# DeadHorsePCB.net
KiCad netlist of a schematic drawn in EAGLE
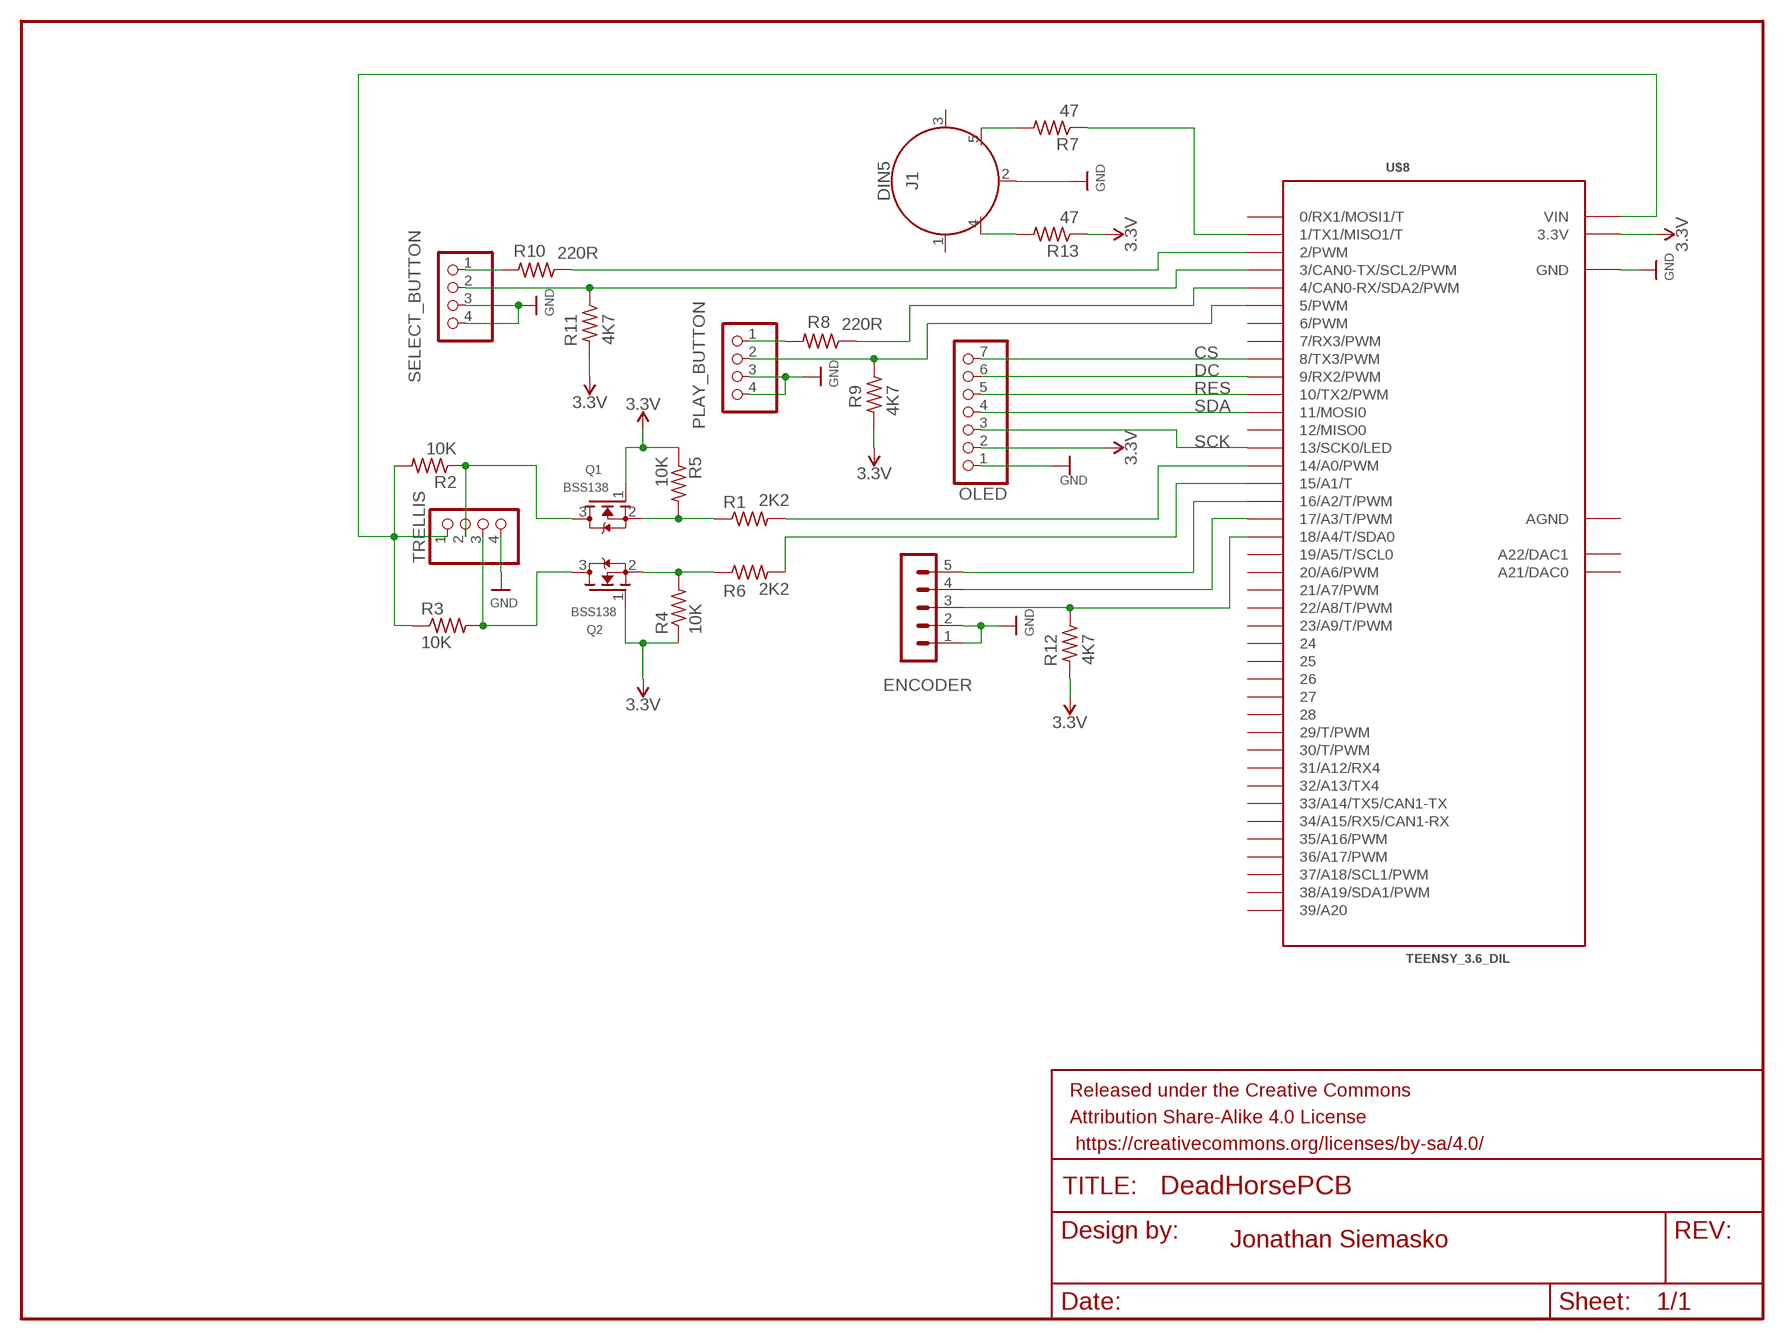
[diagram p0: schematic, sheet 1]

(export (version "E")
  (design (tool "Eeschema 10.0.6"))
  (components
    (comp (ref "ENCODER")
      (value "MA05-1")
      (footprint "eagle-import:MA05-1")
      (libsource (lib "eagle-import") (part "MA05-1"))
    )
    (comp (ref "FRAME1")
      (value "FRAME-LETTER")
      (footprint "eagle-import:CREATIVE_COMMONS")
      (libsource (lib "eagle-import") (part "FRAME-LETTER"))
    )
    (comp (ref "J1")
      (value "DIN5")
      (footprint "eagle-import:DIN5-RA-PTH")
      (libsource (lib "eagle-import") (part "DIN5"))
    )
    (comp (ref "OLED")
      (value "OLED")
      (footprint "eagle-import:1X07")
      (libsource (lib "eagle-import") (part "PINHD-1X7"))
    )
    (comp (ref "PLAY_BUTTON")
      (value "PlayBtn")
      (footprint "eagle-import:1X04")
      (libsource (lib "eagle-import") (part "PINHD-1X4"))
    )
    (comp (ref "Q1")
      (value "BSS138")
      (footprint "eagle-import:SOT23")
      (libsource (lib "eagle-import") (part "MOSFET-NREFLOW"))
    )
    (comp (ref "Q2")
      (value "BSS138")
      (footprint "eagle-import:SOT23")
      (libsource (lib "eagle-import") (part "MOSFET-NREFLOW"))
    )
    (comp (ref "R1")
      (value "2K2")
      (footprint "eagle-import:R0805")
      (libsource (lib "eagle-import") (part "R-US_R0805"))
    )
    (comp (ref "R2")
      (value "10K")
      (footprint "eagle-import:R0805")
      (libsource (lib "eagle-import") (part "R-US_R0805"))
    )
    (comp (ref "R3")
      (value "10K")
      (footprint "eagle-import:R0805")
      (libsource (lib "eagle-import") (part "R-US_R0805"))
    )
    (comp (ref "R4")
      (value "10K")
      (footprint "eagle-import:R0805")
      (libsource (lib "eagle-import") (part "R-US_R0805"))
    )
    (comp (ref "R5")
      (value "10K")
      (footprint "eagle-import:R0805")
      (libsource (lib "eagle-import") (part "R-US_R0805"))
    )
    (comp (ref "R6")
      (value "2K2")
      (footprint "eagle-import:R0805")
      (libsource (lib "eagle-import") (part "R-US_R0805"))
    )
    (comp (ref "R7")
      (value "47")
      (footprint "eagle-import:R0805")
      (libsource (lib "eagle-import") (part "R-US_R0805"))
    )
    (comp (ref "R8")
      (value "220R")
      (footprint "eagle-import:R0805")
      (libsource (lib "eagle-import") (part "R-US_R0805"))
    )
    (comp (ref "R9")
      (value "4K7")
      (footprint "eagle-import:R0805")
      (libsource (lib "eagle-import") (part "R-US_R0805"))
    )
    (comp (ref "R10")
      (value "220R")
      (footprint "eagle-import:R0805")
      (libsource (lib "eagle-import") (part "R-US_R0805"))
    )
    (comp (ref "R11")
      (value "4K7")
      (footprint "eagle-import:R0805")
      (libsource (lib "eagle-import") (part "R-US_R0805"))
    )
    (comp (ref "R12")
      (value "4K7")
      (footprint "eagle-import:R0805")
      (libsource (lib "eagle-import") (part "R-US_R0805"))
    )
    (comp (ref "R13")
      (value "47")
      (footprint "eagle-import:R0805")
      (libsource (lib "eagle-import") (part "R-US_R0805"))
    )
    (comp (ref "SELECT_BUTTON")
      (value "SelectBtn")
      (footprint "eagle-import:1X04")
      (libsource (lib "eagle-import") (part "PINHD-1X4"))
    )
    (comp (ref "TRELLIS")
      (value "TRELLIS")
      (footprint "eagle-import:1X04")
      (libsource (lib "eagle-import") (part "PINHD-1X4"))
    )
    (comp (ref "U$8")
      (value "TEENSY_3.6_DIL")
      (footprint "eagle-import:TEENSY_3.6_DIL")
      (libsource (lib "eagle-import") (part "TEENSY_3.6_DIL"))
    )
  )
  (nets
    (net (code "1") (name "/AGND") (class "Default")
      (node (ref "U$8") (pin "AGND") (pinfunction "AGND_AGND") (pintype "power_in"))
    )
    (net (code "2") (name "/CS") (class "Default")
      (node (ref "OLED") (pin "7") (pinfunction "7_7") (pintype "passive"))
      (node (ref "U$8") (pin "8") (pinfunction "8/TX3/PWM_8") (pintype "bidirectional"))
    )
    (net (code "3") (name "/DC") (class "Default")
      (node (ref "OLED") (pin "6") (pinfunction "6_6") (pintype "passive"))
      (node (ref "U$8") (pin "9") (pinfunction "9/RX2/PWM_9") (pintype "bidirectional"))
    )
    (net (code "4") (name "/RES") (class "Default")
      (node (ref "OLED") (pin "5") (pinfunction "5_5") (pintype "passive"))
      (node (ref "U$8") (pin "10") (pinfunction "10/TX2/PWM_10") (pintype "bidirectional"))
    )
    (net (code "5") (name "/SCK") (class "Default")
      (node (ref "OLED") (pin "3") (pinfunction "3_3") (pintype "passive"))
      (node (ref "U$8") (pin "13") (pinfunction "13/SCK0/LED_13") (pintype "bidirectional"))
    )
    (net (code "6") (name "/SDA") (class "Default")
      (node (ref "OLED") (pin "4") (pinfunction "4_4") (pintype "passive"))
      (node (ref "U$8") (pin "11") (pinfunction "11/MOSI0_11") (pintype "bidirectional"))
    )
    (net (code "7") (name "3.3V") (class "Default")
      (node (ref "OLED") (pin "2") (pinfunction "2_2") (pintype "passive"))
      (node (ref "Q1") (pin "1") (pinfunction "G_1") (pintype "bidirectional"))
      (node (ref "Q2") (pin "1") (pinfunction "G_1") (pintype "bidirectional"))
      (node (ref "R11") (pin "2") (pinfunction "2_2") (pintype "passive"))
      (node (ref "R12") (pin "2") (pinfunction "2_2") (pintype "passive"))
      (node (ref "R13") (pin "1") (pinfunction "1_1") (pintype "passive"))
      (node (ref "R4") (pin "1") (pinfunction "1_1") (pintype "passive"))
      (node (ref "R5") (pin "1") (pinfunction "1_1") (pintype "passive"))
      (node (ref "R9") (pin "2") (pinfunction "2_2") (pintype "passive"))
      (node (ref "U$8") (pin "3.3V") (pinfunction "3.3V_3.3V") (pintype "power_in"))
      (node (ref "U$8") (pin "3.3V3") (pinfunction "3.3V_3.3V3") (pintype "power_in"))
    )
    (net (code "8") (name "GND") (class "Default")
      (node (ref "ENCODER") (pin "1") (pinfunction "1_1") (pintype "passive"))
      (node (ref "ENCODER") (pin "2") (pinfunction "2_2") (pintype "passive"))
      (node (ref "J1") (pin "2") (pinfunction "2_2") (pintype "bidirectional"))
      (node (ref "OLED") (pin "1") (pinfunction "1_1") (pintype "passive"))
      (node (ref "PLAY_BUTTON") (pin "3") (pinfunction "3_3") (pintype "passive"))
      (node (ref "PLAY_BUTTON") (pin "4") (pinfunction "4_4") (pintype "passive"))
      (node (ref "SELECT_BUTTON") (pin "3") (pinfunction "3_3") (pintype "passive"))
      (node (ref "SELECT_BUTTON") (pin "4") (pinfunction "4_4") (pintype "passive"))
      (node (ref "TRELLIS") (pin "4") (pinfunction "4_4") (pintype "passive"))
      (node (ref "U$8") (pin "GND") (pinfunction "GND_GND") (pintype "power_in"))
      (node (ref "U$8") (pin "GND1") (pinfunction "GND_GND1") (pintype "power_in"))
    )
    (net (code "9") (name "Net-(J1-Pad4)") (class "Default")
      (node (ref "J1") (pin "4") (pinfunction "4_4") (pintype "bidirectional"))
      (node (ref "R13") (pin "2") (pinfunction "2_2") (pintype "passive"))
    )
    (net (code "10") (name "Net-(J1-Pad5)") (class "Default")
      (node (ref "J1") (pin "5") (pinfunction "5_5") (pintype "bidirectional"))
      (node (ref "R7") (pin "2") (pinfunction "2_2") (pintype "passive"))
    )
    (net (code "11") (name "Net-(PLAY_BUTTON-Pad1)") (class "Default")
      (node (ref "PLAY_BUTTON") (pin "1") (pinfunction "1_1") (pintype "passive"))
      (node (ref "R8") (pin "2") (pinfunction "2_2") (pintype "passive"))
    )
    (net (code "12") (name "Net-(Q1-D)") (class "Default")
      (node (ref "Q1") (pin "3") (pinfunction "D_3") (pintype "bidirectional"))
      (node (ref "R2") (pin "1") (pinfunction "1_1") (pintype "passive"))
      (node (ref "TRELLIS") (pin "2") (pinfunction "2_2") (pintype "passive"))
    )
    (net (code "13") (name "Net-(Q1-S)") (class "Default")
      (node (ref "Q1") (pin "2") (pinfunction "S_2") (pintype "bidirectional"))
      (node (ref "R1") (pin "1") (pinfunction "1_1") (pintype "passive"))
      (node (ref "R5") (pin "2") (pinfunction "2_2") (pintype "passive"))
    )
    (net (code "14") (name "Net-(Q2-D)") (class "Default")
      (node (ref "Q2") (pin "3") (pinfunction "D_3") (pintype "bidirectional"))
      (node (ref "R3") (pin "2") (pinfunction "2_2") (pintype "passive"))
      (node (ref "TRELLIS") (pin "3") (pinfunction "3_3") (pintype "passive"))
    )
    (net (code "15") (name "Net-(Q2-S)") (class "Default")
      (node (ref "Q2") (pin "2") (pinfunction "S_2") (pintype "bidirectional"))
      (node (ref "R4") (pin "2") (pinfunction "2_2") (pintype "passive"))
      (node (ref "R6") (pin "1") (pinfunction "1_1") (pintype "passive"))
    )
    (net (code "16") (name "Net-(R2-Pad2)") (class "Default")
      (node (ref "R2") (pin "2") (pinfunction "2_2") (pintype "passive"))
      (node (ref "R3") (pin "1") (pinfunction "1_1") (pintype "passive"))
      (node (ref "TRELLIS") (pin "1") (pinfunction "1_1") (pintype "passive"))
      (node (ref "U$8") (pin "VIN") (pinfunction "VIN_VIN") (pintype "power_in"))
    )
    (net (code "17") (name "Net-(R10-Pad2)") (class "Default")
      (node (ref "R10") (pin "2") (pinfunction "2_2") (pintype "passive"))
      (node (ref "SELECT_BUTTON") (pin "1") (pinfunction "1_1") (pintype "passive"))
    )
    (net (code "18") (name "Net-(U$8-1{slash}TX1{slash}MISO1{slash}T)") (class "Default")
      (node (ref "R7") (pin "1") (pinfunction "1_1") (pintype "passive"))
      (node (ref "U$8") (pin "1") (pinfunction "1/TX1/MISO1/T_1") (pintype "bidirectional"))
    )
    (net (code "19") (name "Net-(U$8-2{slash}PWM)") (class "Default")
      (node (ref "R10") (pin "1") (pinfunction "1_1") (pintype "passive"))
      (node (ref "U$8") (pin "2") (pinfunction "2/PWM_2") (pintype "bidirectional"))
    )
    (net (code "20") (name "Net-(U$8-3{slash}CAN0-TX{slash}SCL2{slash}PWM)") (class "Default")
      (node (ref "R11") (pin "1") (pinfunction "1_1") (pintype "passive"))
      (node (ref "SELECT_BUTTON") (pin "2") (pinfunction "2_2") (pintype "passive"))
      (node (ref "U$8") (pin "3") (pinfunction "3/CAN0-TX/SCL2/PWM_3") (pintype "bidirectional"))
    )
    (net (code "21") (name "Net-(U$8-4{slash}CAN0-RX{slash}SDA2{slash}PWM)") (class "Default")
      (node (ref "R8") (pin "1") (pinfunction "1_1") (pintype "passive"))
      (node (ref "U$8") (pin "4") (pinfunction "4/CAN0-RX/SDA2/PWM_4") (pintype "bidirectional"))
    )
    (net (code "22") (name "Net-(U$8-5{slash}PWM)") (class "Default")
      (node (ref "PLAY_BUTTON") (pin "2") (pinfunction "2_2") (pintype "passive"))
      (node (ref "R9") (pin "1") (pinfunction "1_1") (pintype "passive"))
      (node (ref "U$8") (pin "5") (pinfunction "5/PWM_5") (pintype "bidirectional"))
    )
    (net (code "23") (name "Net-(U$8-14{slash}A0{slash}PWM)") (class "Default")
      (node (ref "R1") (pin "2") (pinfunction "2_2") (pintype "passive"))
      (node (ref "U$8") (pin "14/A0") (pinfunction "14/A0/PWM_14/A0") (pintype "bidirectional"))
    )
    (net (code "24") (name "Net-(U$8-15{slash}A1{slash}T)") (class "Default")
      (node (ref "R6") (pin "2") (pinfunction "2_2") (pintype "passive"))
      (node (ref "U$8") (pin "15/A1") (pinfunction "15/A1/T_15/A1") (pintype "bidirectional"))
    )
    (net (code "25") (name "Net-(U$8-16{slash}A2{slash}T{slash}PWM)") (class "Default")
      (node (ref "ENCODER") (pin "5") (pinfunction "5_5") (pintype "passive"))
      (node (ref "U$8") (pin "16/A2") (pinfunction "16/A2/T/PWM_16/A2") (pintype "bidirectional"))
    )
    (net (code "26") (name "Net-(U$8-17{slash}A3{slash}T{slash}PWM)") (class "Default")
      (node (ref "ENCODER") (pin "4") (pinfunction "4_4") (pintype "passive"))
      (node (ref "U$8") (pin "17/A3") (pinfunction "17/A3/T/PWM_17/A3") (pintype "bidirectional"))
    )
    (net (code "27") (name "Net-(U$8-18{slash}A4{slash}T{slash}SDA0)") (class "Default")
      (node (ref "ENCODER") (pin "3") (pinfunction "3_3") (pintype "passive"))
      (node (ref "R12") (pin "1") (pinfunction "1_1") (pintype "passive"))
      (node (ref "U$8") (pin "18/A4") (pinfunction "18/A4/T/SDA0_18/A4") (pintype "bidirectional"))
    )
    (net (code "28") (name "unconnected-(J1-Pad1)") (class "Default")
      (node (ref "J1") (pin "1") (pinfunction "1_1") (pintype "bidirectional"))
    )
    (net (code "29") (name "unconnected-(J1-Pad3)") (class "Default")
      (node (ref "J1") (pin "3") (pinfunction "3_3") (pintype "bidirectional"))
    )
    (net (code "30") (name "unconnected-(U$8-0{slash}RX1{slash}MOSI1{slash}T-Pad0)") (class "Default")
      (node (ref "U$8") (pin "0") (pinfunction "0/RX1/MOSI1/T_0") (pintype "bidirectional"))
    )
    (net (code "31") (name "unconnected-(U$8-6{slash}PWM-Pad6)") (class "Default")
      (node (ref "U$8") (pin "6") (pinfunction "6/PWM_6") (pintype "bidirectional"))
    )
    (net (code "32") (name "unconnected-(U$8-7{slash}RX3{slash}PWM-Pad7)") (class "Default")
      (node (ref "U$8") (pin "7") (pinfunction "7/RX3/PWM_7") (pintype "bidirectional"))
    )
    (net (code "33") (name "unconnected-(U$8-12{slash}MISO0-Pad12)") (class "Default")
      (node (ref "U$8") (pin "12") (pinfunction "12/MISO0_12") (pintype "bidirectional"))
    )
    (net (code "34") (name "unconnected-(U$8-19{slash}A5{slash}T{slash}SCL0-Pad19{slash}A5)") (class "Default")
      (node (ref "U$8") (pin "19/A5") (pinfunction "19/A5/T/SCL0_19/A5") (pintype "bidirectional"))
    )
    (net (code "35") (name "unconnected-(U$8-20{slash}A6{slash}PWM-Pad20{slash}A6)") (class "Default")
      (node (ref "U$8") (pin "20/A6") (pinfunction "20/A6/PWM_20/A6") (pintype "bidirectional"))
    )
    (net (code "36") (name "unconnected-(U$8-21{slash}A7{slash}PWM-Pad21{slash}A7)") (class "Default")
      (node (ref "U$8") (pin "21/A7") (pinfunction "21/A7/PWM_21/A7") (pintype "bidirectional"))
    )
    (net (code "37") (name "unconnected-(U$8-22{slash}A8{slash}T{slash}PWM-Pad22{slash}A8)") (class "Default")
      (node (ref "U$8") (pin "22/A8") (pinfunction "22/A8/T/PWM_22/A8") (pintype "bidirectional"))
    )
    (net (code "38") (name "unconnected-(U$8-23{slash}A9{slash}T{slash}PWM-Pad23{slash}A9)") (class "Default")
      (node (ref "U$8") (pin "23/A9") (pinfunction "23/A9/T/PWM_23/A9") (pintype "bidirectional"))
    )
    (net (code "39") (name "unconnected-(U$8-29{slash}T{slash}PWM-Pad29)") (class "Default")
      (node (ref "U$8") (pin "29") (pinfunction "29/T/PWM_29") (pintype "bidirectional"))
    )
    (net (code "40") (name "unconnected-(U$8-30{slash}T{slash}PWM-Pad30)") (class "Default")
      (node (ref "U$8") (pin "30") (pinfunction "30/T/PWM_30") (pintype "bidirectional"))
    )
    (net (code "41") (name "unconnected-(U$8-31{slash}A12{slash}RX4-Pad31{slash}A12)") (class "Default")
      (node (ref "U$8") (pin "31/A12") (pinfunction "31/A12/RX4_31/A12") (pintype "bidirectional"))
    )
    (net (code "42") (name "unconnected-(U$8-32{slash}A13{slash}TX4-Pad32{slash}A13)") (class "Default")
      (node (ref "U$8") (pin "32/A13") (pinfunction "32/A13/TX4_32/A13") (pintype "bidirectional"))
    )
    (net (code "43") (name "unconnected-(U$8-33{slash}A14{slash}TX5{slash}CAN1-TX-Pad33{slash}A14)") (class "Default")
      (node (ref "U$8") (pin "33/A14") (pinfunction "33/A14/TX5/CAN1-TX_33/A14") (pintype "bidirectional"))
    )
    (net (code "44") (name "unconnected-(U$8-34{slash}A15{slash}RX5{slash}CAN1-RX-Pad34{slash}A15)") (class "Default")
      (node (ref "U$8") (pin "34/A15") (pinfunction "34/A15/RX5/CAN1-RX_34/A15") (pintype "bidirectional"))
    )
    (net (code "45") (name "unconnected-(U$8-35{slash}A16{slash}PWM-Pad35{slash}A16)") (class "Default")
      (node (ref "U$8") (pin "35/A16") (pinfunction "35/A16/PWM_35/A16") (pintype "bidirectional"))
    )
    (net (code "46") (name "unconnected-(U$8-36{slash}A17{slash}PWM-Pad36{slash}A17)") (class "Default")
      (node (ref "U$8") (pin "36/A17") (pinfunction "36/A17/PWM_36/A17") (pintype "bidirectional"))
    )
    (net (code "47") (name "unconnected-(U$8-37{slash}A18{slash}SCL1{slash}PWM-Pad37{slash}A18)") (class "Default")
      (node (ref "U$8") (pin "37/A18") (pinfunction "37/A18/SCL1/PWM_37/A18") (pintype "bidirectional"))
    )
    (net (code "48") (name "unconnected-(U$8-38{slash}A19{slash}SDA1{slash}PWM-Pad38{slash}A19)") (class "Default")
      (node (ref "U$8") (pin "38/A19") (pinfunction "38/A19/SDA1/PWM_38/A19") (pintype "bidirectional"))
    )
    (net (code "49") (name "unconnected-(U$8-A21{slash}DAC0-PadA21)") (class "Default")
      (node (ref "U$8") (pin "A21") (pinfunction "A21/DAC0_A21") (pintype "bidirectional"))
    )
    (net (code "50") (name "unconnected-(U$8-A22{slash}DAC1-PadA22)") (class "Default")
      (node (ref "U$8") (pin "A22") (pinfunction "A22/DAC1_A22") (pintype "bidirectional"))
    )
    (net (code "51") (name "unconnected-(U$8-Pad24)") (class "Default")
      (node (ref "U$8") (pin "24") (pinfunction "24_24") (pintype "bidirectional"))
    )
    (net (code "52") (name "unconnected-(U$8-Pad25)") (class "Default")
      (node (ref "U$8") (pin "25") (pinfunction "25_25") (pintype "bidirectional"))
    )
    (net (code "53") (name "unconnected-(U$8-Pad26)") (class "Default")
      (node (ref "U$8") (pin "26") (pinfunction "26_26") (pintype "bidirectional"))
    )
    (net (code "54") (name "unconnected-(U$8-Pad27)") (class "Default")
      (node (ref "U$8") (pin "27") (pinfunction "27_27") (pintype "bidirectional"))
    )
    (net (code "55") (name "unconnected-(U$8-Pad28)") (class "Default")
      (node (ref "U$8") (pin "28") (pinfunction "28_28") (pintype "bidirectional"))
    )
    (net (code "56") (name "unconnected-(U$8-Pad39{slash}A20)") (class "Default")
      (node (ref "U$8") (pin "39/A20") (pinfunction "39/A20_39/A20") (pintype "bidirectional"))
    )
  )
)
